# tinyg_g2_breakout.net
KiCad netlist of a schematic drawn in EAGLE
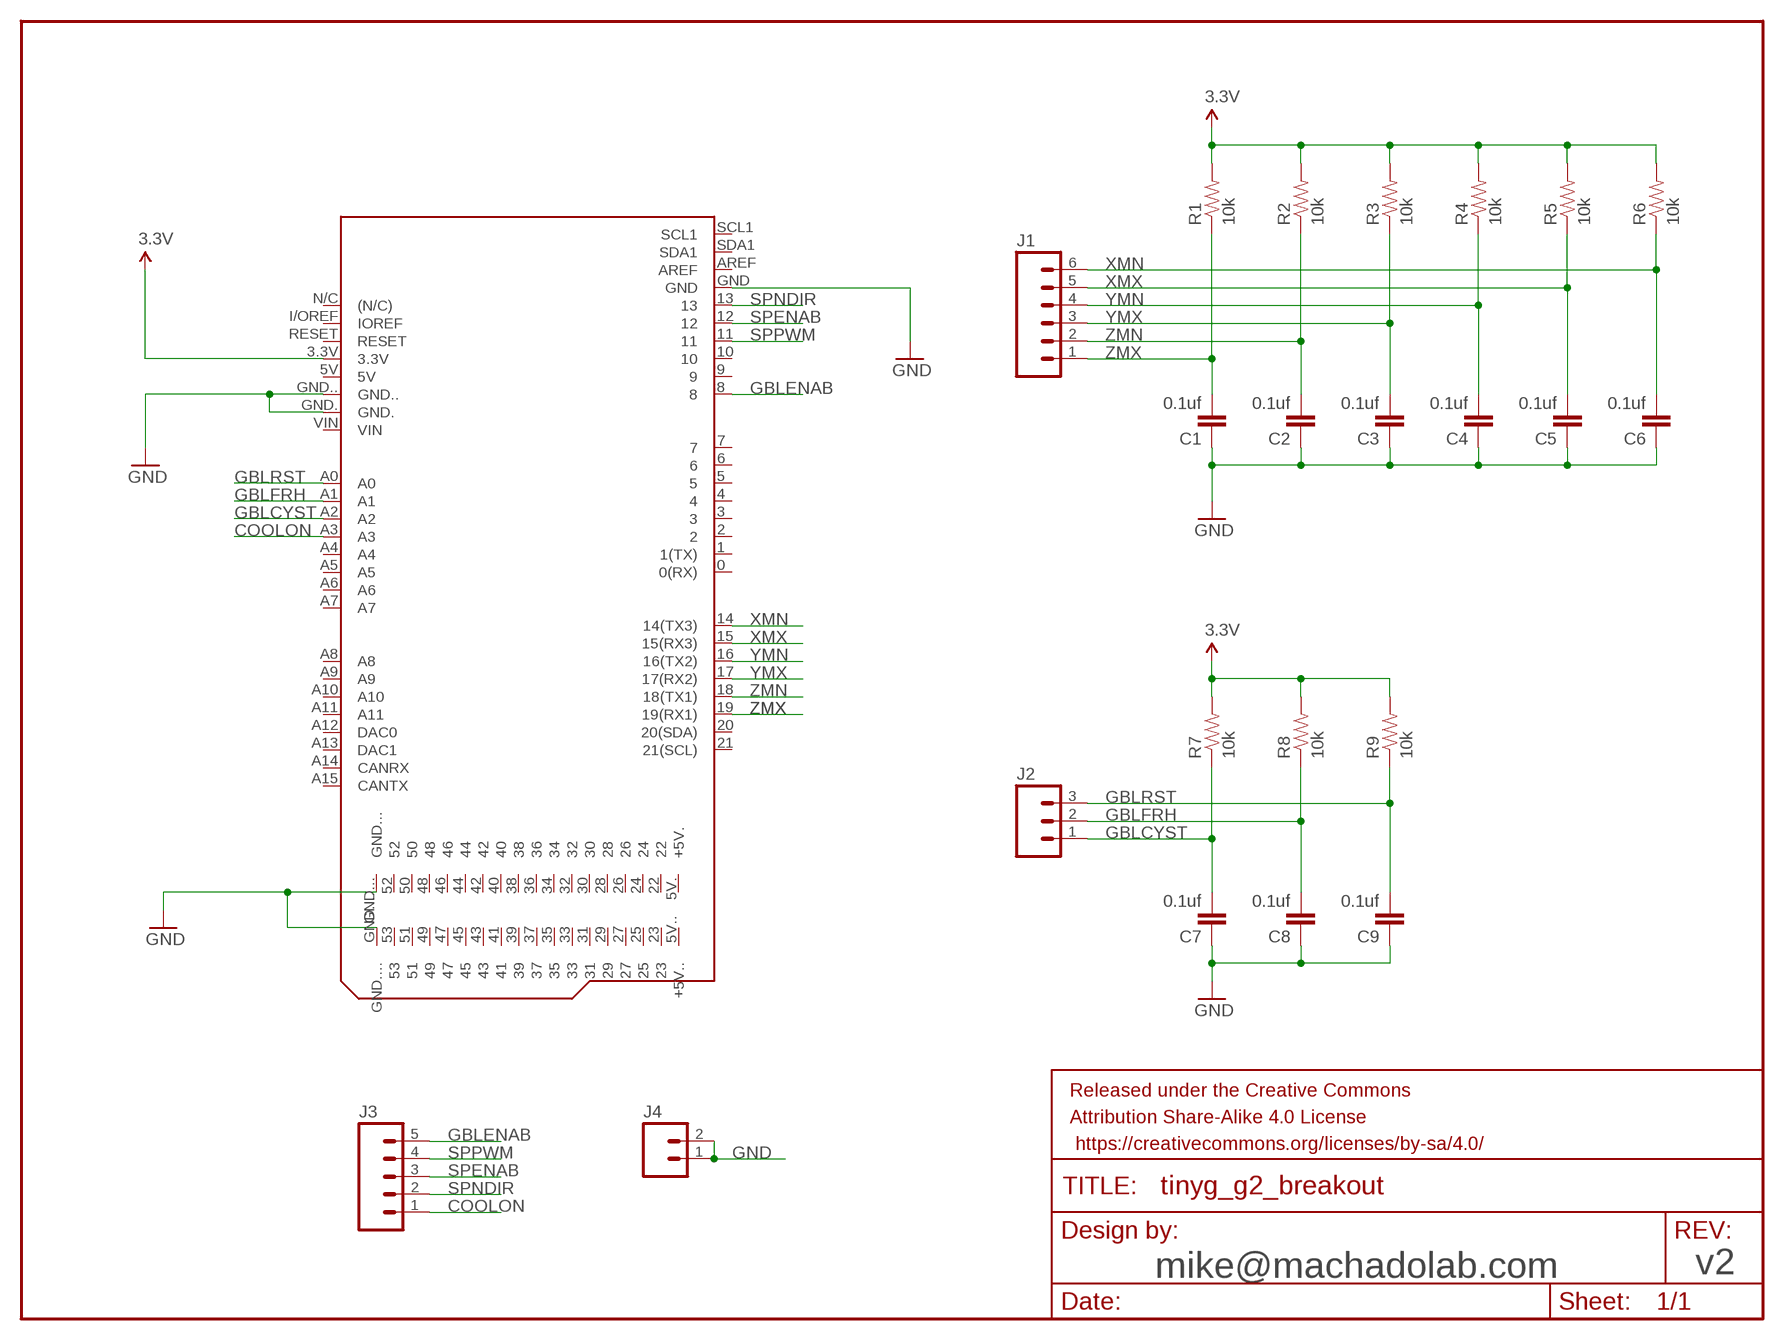
[diagram p0: schematic, sheet 1]

(export (version "E")
  (design (tool "Eeschema 10.0.6"))
  (components
    (comp (ref "C1")
      (value "0.1uf")
      (footprint "eagle-import:CAP-PTH-SMALL")
      (libsource (lib "eagle-import") (part "CAPPTH"))
    )
    (comp (ref "C2")
      (value "0.1uf")
      (footprint "eagle-import:CAP-PTH-SMALL")
      (libsource (lib "eagle-import") (part "CAPPTH"))
    )
    (comp (ref "C3")
      (value "0.1uf")
      (footprint "eagle-import:CAP-PTH-SMALL")
      (libsource (lib "eagle-import") (part "CAPPTH"))
    )
    (comp (ref "C4")
      (value "0.1uf")
      (footprint "eagle-import:CAP-PTH-SMALL")
      (libsource (lib "eagle-import") (part "CAPPTH"))
    )
    (comp (ref "C5")
      (value "0.1uf")
      (footprint "eagle-import:CAP-PTH-SMALL")
      (libsource (lib "eagle-import") (part "CAPPTH"))
    )
    (comp (ref "C6")
      (value "0.1uf")
      (footprint "eagle-import:CAP-PTH-SMALL")
      (libsource (lib "eagle-import") (part "CAPPTH"))
    )
    (comp (ref "C7")
      (value "0.1uf")
      (footprint "eagle-import:CAP-PTH-SMALL")
      (libsource (lib "eagle-import") (part "CAPPTH"))
    )
    (comp (ref "C8")
      (value "0.1uf")
      (footprint "eagle-import:CAP-PTH-SMALL")
      (libsource (lib "eagle-import") (part "CAPPTH"))
    )
    (comp (ref "C9")
      (value "0.1uf")
      (footprint "eagle-import:CAP-PTH-SMALL")
      (libsource (lib "eagle-import") (part "CAPPTH"))
    )
    (comp (ref "FRAME1")
      (value "v1")
      (footprint "eagle-import:CREATIVE_COMMONS")
      (libsource (lib "eagle-import") (part "FRAME-LETTER"))
    )
    (comp (ref "J1")
      (value "M06SILK_FEMALE_PTH")
      (footprint "eagle-import:1X06")
      (libsource (lib "eagle-import") (part "M06SILK_FEMALE_PTH"))
    )
    (comp (ref "J2")
      (value "M03PTH")
      (footprint "eagle-import:1X03")
      (libsource (lib "eagle-import") (part "M03PTH"))
    )
    (comp (ref "J3")
      (value "M05PTH")
      (footprint "eagle-import:1X05")
      (libsource (lib "eagle-import") (part "M05PTH"))
    )
    (comp (ref "J4")
      (value "M02PTH")
      (footprint "eagle-import:1X02")
      (libsource (lib "eagle-import") (part "M02PTH"))
    )
    (comp (ref "PCB1")
      (value "ARDUINO_DUE_SHIELD")
      (footprint "eagle-import:ARDUINO_DUE_SHIELD")
      (libsource (lib "eagle-import") (part "ARDUINO_DUE_SHIELD"))
    )
    (comp (ref "R1")
      (value "10k")
      (footprint "eagle-import:AXIAL-0.3")
      (libsource (lib "eagle-import") (part "RESISTORAXIAL-0.3"))
    )
    (comp (ref "R2")
      (value "10k")
      (footprint "eagle-import:AXIAL-0.3")
      (libsource (lib "eagle-import") (part "RESISTORAXIAL-0.3"))
    )
    (comp (ref "R3")
      (value "10k")
      (footprint "eagle-import:AXIAL-0.3")
      (libsource (lib "eagle-import") (part "RESISTORAXIAL-0.3"))
    )
    (comp (ref "R4")
      (value "10k")
      (footprint "eagle-import:AXIAL-0.3")
      (libsource (lib "eagle-import") (part "RESISTORAXIAL-0.3"))
    )
    (comp (ref "R5")
      (value "10k")
      (footprint "eagle-import:AXIAL-0.3")
      (libsource (lib "eagle-import") (part "RESISTORAXIAL-0.3"))
    )
    (comp (ref "R6")
      (value "10k")
      (footprint "eagle-import:AXIAL-0.3")
      (libsource (lib "eagle-import") (part "RESISTORAXIAL-0.3"))
    )
    (comp (ref "R7")
      (value "10k")
      (footprint "eagle-import:AXIAL-0.3")
      (libsource (lib "eagle-import") (part "RESISTORAXIAL-0.3"))
    )
    (comp (ref "R8")
      (value "10k")
      (footprint "eagle-import:AXIAL-0.3")
      (libsource (lib "eagle-import") (part "RESISTORAXIAL-0.3"))
    )
    (comp (ref "R9")
      (value "10k")
      (footprint "eagle-import:AXIAL-0.3")
      (libsource (lib "eagle-import") (part "RESISTORAXIAL-0.3"))
    )
  )
  (nets
    (net (code "1") (name "/COOLON") (class "Default")
      (node (ref "J3") (pin "1") (pinfunction "1_1") (pintype "passive"))
      (node (ref "PCB1") (pin "A3") (pinfunction "A3_A3") (pintype "bidirectional"))
    )
    (net (code "2") (name "/GBLCYST") (class "Default")
      (node (ref "C7") (pin "2") (pinfunction "2_2") (pintype "passive"))
      (node (ref "J2") (pin "1") (pinfunction "1_1") (pintype "passive"))
      (node (ref "PCB1") (pin "A2") (pinfunction "A2_A2") (pintype "bidirectional"))
      (node (ref "R7") (pin "P$1") (pinfunction "1_P$1") (pintype "passive"))
    )
    (net (code "3") (name "/GBLENAB") (class "Default")
      (node (ref "J3") (pin "5") (pinfunction "5_5") (pintype "passive"))
      (node (ref "PCB1") (pin "8") (pinfunction "8_8") (pintype "bidirectional"))
    )
    (net (code "4") (name "/GBLFRH") (class "Default")
      (node (ref "C8") (pin "2") (pinfunction "2_2") (pintype "passive"))
      (node (ref "J2") (pin "2") (pinfunction "2_2") (pintype "passive"))
      (node (ref "PCB1") (pin "A1") (pinfunction "A1_A1") (pintype "bidirectional"))
      (node (ref "R8") (pin "P$1") (pinfunction "1_P$1") (pintype "passive"))
    )
    (net (code "5") (name "/GBLRST") (class "Default")
      (node (ref "C9") (pin "2") (pinfunction "2_2") (pintype "passive"))
      (node (ref "J2") (pin "3") (pinfunction "3_3") (pintype "passive"))
      (node (ref "PCB1") (pin "A0") (pinfunction "A0_A0") (pintype "bidirectional"))
      (node (ref "R9") (pin "P$1") (pinfunction "1_P$1") (pintype "passive"))
    )
    (net (code "6") (name "/SPENAB") (class "Default")
      (node (ref "J3") (pin "3") (pinfunction "3_3") (pintype "passive"))
      (node (ref "PCB1") (pin "12") (pinfunction "12_12") (pintype "bidirectional"))
    )
    (net (code "7") (name "/SPNDIR") (class "Default")
      (node (ref "J3") (pin "2") (pinfunction "2_2") (pintype "passive"))
      (node (ref "PCB1") (pin "13") (pinfunction "13_13") (pintype "bidirectional"))
    )
    (net (code "8") (name "/SPPWM") (class "Default")
      (node (ref "J3") (pin "4") (pinfunction "4_4") (pintype "passive"))
      (node (ref "PCB1") (pin "11") (pinfunction "11_11") (pintype "bidirectional"))
    )
    (net (code "9") (name "/XMN") (class "Default")
      (node (ref "C6") (pin "2") (pinfunction "2_2") (pintype "passive"))
      (node (ref "J1") (pin "6") (pinfunction "6_6") (pintype "passive"))
      (node (ref "PCB1") (pin "14") (pinfunction "14(TX3)_14") (pintype "bidirectional"))
      (node (ref "R6") (pin "P$1") (pinfunction "1_P$1") (pintype "passive"))
    )
    (net (code "10") (name "/XMX") (class "Default")
      (node (ref "C5") (pin "2") (pinfunction "2_2") (pintype "passive"))
      (node (ref "J1") (pin "5") (pinfunction "5_5") (pintype "passive"))
      (node (ref "PCB1") (pin "15") (pinfunction "15(RX3)_15") (pintype "bidirectional"))
      (node (ref "R5") (pin "P$1") (pinfunction "1_P$1") (pintype "passive"))
    )
    (net (code "11") (name "/YMN") (class "Default")
      (node (ref "C4") (pin "2") (pinfunction "2_2") (pintype "passive"))
      (node (ref "J1") (pin "4") (pinfunction "4_4") (pintype "passive"))
      (node (ref "PCB1") (pin "16") (pinfunction "16(TX2)_16") (pintype "bidirectional"))
      (node (ref "R4") (pin "P$1") (pinfunction "1_P$1") (pintype "passive"))
    )
    (net (code "12") (name "/YMX") (class "Default")
      (node (ref "C3") (pin "2") (pinfunction "2_2") (pintype "passive"))
      (node (ref "J1") (pin "3") (pinfunction "3_3") (pintype "passive"))
      (node (ref "PCB1") (pin "17") (pinfunction "17(RX2)_17") (pintype "bidirectional"))
      (node (ref "R3") (pin "P$1") (pinfunction "1_P$1") (pintype "passive"))
    )
    (net (code "13") (name "/ZMN") (class "Default")
      (node (ref "C2") (pin "2") (pinfunction "2_2") (pintype "passive"))
      (node (ref "J1") (pin "2") (pinfunction "2_2") (pintype "passive"))
      (node (ref "PCB1") (pin "18") (pinfunction "18(TX1)_18") (pintype "bidirectional"))
      (node (ref "R2") (pin "P$1") (pinfunction "1_P$1") (pintype "passive"))
    )
    (net (code "14") (name "/ZMX") (class "Default")
      (node (ref "C1") (pin "2") (pinfunction "2_2") (pintype "passive"))
      (node (ref "J1") (pin "1") (pinfunction "1_1") (pintype "passive"))
      (node (ref "PCB1") (pin "19") (pinfunction "19(RX1)_19") (pintype "bidirectional"))
      (node (ref "R1") (pin "P$1") (pinfunction "1_P$1") (pintype "passive"))
    )
    (net (code "15") (name "3.3V") (class "Default")
      (node (ref "PCB1") (pin "3.3V") (pinfunction "3.3V_3.3V") (pintype "bidirectional"))
      (node (ref "R1") (pin "P$2") (pinfunction "2_P$2") (pintype "passive"))
      (node (ref "R2") (pin "P$2") (pinfunction "2_P$2") (pintype "passive"))
      (node (ref "R3") (pin "P$2") (pinfunction "2_P$2") (pintype "passive"))
      (node (ref "R4") (pin "P$2") (pinfunction "2_P$2") (pintype "passive"))
      (node (ref "R5") (pin "P$2") (pinfunction "2_P$2") (pintype "passive"))
      (node (ref "R6") (pin "P$2") (pinfunction "2_P$2") (pintype "passive"))
      (node (ref "R7") (pin "P$2") (pinfunction "2_P$2") (pintype "passive"))
      (node (ref "R8") (pin "P$2") (pinfunction "2_P$2") (pintype "passive"))
      (node (ref "R9") (pin "P$2") (pinfunction "2_P$2") (pintype "passive"))
    )
    (net (code "16") (name "GND") (class "Default")
      (node (ref "C1") (pin "1") (pinfunction "1_1") (pintype "passive"))
      (node (ref "C2") (pin "1") (pinfunction "1_1") (pintype "passive"))
      (node (ref "C3") (pin "1") (pinfunction "1_1") (pintype "passive"))
      (node (ref "C4") (pin "1") (pinfunction "1_1") (pintype "passive"))
      (node (ref "C5") (pin "1") (pinfunction "1_1") (pintype "passive"))
      (node (ref "C6") (pin "1") (pinfunction "1_1") (pintype "passive"))
      (node (ref "C7") (pin "1") (pinfunction "1_1") (pintype "passive"))
      (node (ref "C8") (pin "1") (pinfunction "1_1") (pintype "passive"))
      (node (ref "C9") (pin "1") (pinfunction "1_1") (pintype "passive"))
      (node (ref "J4") (pin "1") (pinfunction "1_1") (pintype "passive"))
      (node (ref "J4") (pin "2") (pinfunction "2_2") (pintype "passive"))
      (node (ref "PCB1") (pin "GND") (pinfunction "GND_GND") (pintype "bidirectional"))
      (node (ref "PCB1") (pin "GND.") (pinfunction "GND._GND.") (pintype "bidirectional"))
      (node (ref "PCB1") (pin "GND..") (pinfunction "GND.._GND..") (pintype "bidirectional"))
      (node (ref "PCB1") (pin "GND...") (pinfunction "GND..._GND...") (pintype "bidirectional"))
      (node (ref "PCB1") (pin "GND....") (pinfunction "GND...._GND....") (pintype "bidirectional"))
    )
    (net (code "17") (name "unconnected-(PCB1-(N{slash}C)-PadN{slash}C)") (class "Default")
      (node (ref "PCB1") (pin "N/C") (pinfunction "(N/C)_N/C") (pintype "bidirectional"))
    )
    (net (code "18") (name "unconnected-(PCB1-+5V.-Pad5V.)") (class "Default")
      (node (ref "PCB1") (pin "5V.") (pinfunction "+5V._5V.") (pintype "bidirectional"))
    )
    (net (code "19") (name "unconnected-(PCB1-+5V..-Pad5V..)") (class "Default")
      (node (ref "PCB1") (pin "5V..") (pinfunction "+5V.._5V..") (pintype "bidirectional"))
    )
    (net (code "20") (name "unconnected-(PCB1-0(RX)-Pad0)") (class "Default")
      (node (ref "PCB1") (pin "0") (pinfunction "0(RX)_0") (pintype "bidirectional"))
    )
    (net (code "21") (name "unconnected-(PCB1-1(TX)-Pad1)") (class "Default")
      (node (ref "PCB1") (pin "1") (pinfunction "1(TX)_1") (pintype "bidirectional"))
    )
    (net (code "22") (name "unconnected-(PCB1-20(SDA)-Pad20)") (class "Default")
      (node (ref "PCB1") (pin "20") (pinfunction "20(SDA)_20") (pintype "bidirectional"))
    )
    (net (code "23") (name "unconnected-(PCB1-21(SCL)-Pad21)") (class "Default")
      (node (ref "PCB1") (pin "21") (pinfunction "21(SCL)_21") (pintype "bidirectional"))
    )
    (net (code "24") (name "unconnected-(PCB1-CANRX-PadA14)") (class "Default")
      (node (ref "PCB1") (pin "A14") (pinfunction "CANRX_A14") (pintype "bidirectional"))
    )
    (net (code "25") (name "unconnected-(PCB1-CANTX-PadA15)") (class "Default")
      (node (ref "PCB1") (pin "A15") (pinfunction "CANTX_A15") (pintype "bidirectional"))
    )
    (net (code "26") (name "unconnected-(PCB1-DAC0-PadA12)") (class "Default")
      (node (ref "PCB1") (pin "A12") (pinfunction "DAC0_A12") (pintype "bidirectional"))
    )
    (net (code "27") (name "unconnected-(PCB1-DAC1-PadA13)") (class "Default")
      (node (ref "PCB1") (pin "A13") (pinfunction "DAC1_A13") (pintype "bidirectional"))
    )
    (net (code "28") (name "unconnected-(PCB1-IOREF-PadI{slash}OREF)") (class "Default")
      (node (ref "PCB1") (pin "I/OREF") (pinfunction "IOREF_I/OREF") (pintype "bidirectional"))
    )
    (net (code "29") (name "unconnected-(PCB1-Pad2)") (class "Default")
      (node (ref "PCB1") (pin "2") (pinfunction "2_2") (pintype "bidirectional"))
    )
    (net (code "30") (name "unconnected-(PCB1-Pad3)") (class "Default")
      (node (ref "PCB1") (pin "3") (pinfunction "3_3") (pintype "bidirectional"))
    )
    (net (code "31") (name "unconnected-(PCB1-Pad4)") (class "Default")
      (node (ref "PCB1") (pin "4") (pinfunction "4_4") (pintype "bidirectional"))
    )
    (net (code "32") (name "unconnected-(PCB1-Pad5)") (class "Default")
      (node (ref "PCB1") (pin "5") (pinfunction "5_5") (pintype "bidirectional"))
    )
    (net (code "33") (name "unconnected-(PCB1-Pad5V)") (class "Default")
      (node (ref "PCB1") (pin "5V") (pinfunction "5V_5V") (pintype "bidirectional"))
    )
    (net (code "34") (name "unconnected-(PCB1-Pad6)") (class "Default")
      (node (ref "PCB1") (pin "6") (pinfunction "6_6") (pintype "bidirectional"))
    )
    (net (code "35") (name "unconnected-(PCB1-Pad7)") (class "Default")
      (node (ref "PCB1") (pin "7") (pinfunction "7_7") (pintype "bidirectional"))
    )
    (net (code "36") (name "unconnected-(PCB1-Pad9)") (class "Default")
      (node (ref "PCB1") (pin "9") (pinfunction "9_9") (pintype "bidirectional"))
    )
    (net (code "37") (name "unconnected-(PCB1-Pad10)") (class "Default")
      (node (ref "PCB1") (pin "10") (pinfunction "10_10") (pintype "bidirectional"))
    )
    (net (code "38") (name "unconnected-(PCB1-Pad22)") (class "Default")
      (node (ref "PCB1") (pin "22") (pinfunction "22_22") (pintype "bidirectional"))
    )
    (net (code "39") (name "unconnected-(PCB1-Pad23)") (class "Default")
      (node (ref "PCB1") (pin "23") (pinfunction "23_23") (pintype "bidirectional"))
    )
    (net (code "40") (name "unconnected-(PCB1-Pad24)") (class "Default")
      (node (ref "PCB1") (pin "24") (pinfunction "24_24") (pintype "bidirectional"))
    )
    (net (code "41") (name "unconnected-(PCB1-Pad25)") (class "Default")
      (node (ref "PCB1") (pin "25") (pinfunction "25_25") (pintype "bidirectional"))
    )
    (net (code "42") (name "unconnected-(PCB1-Pad26)") (class "Default")
      (node (ref "PCB1") (pin "26") (pinfunction "26_26") (pintype "bidirectional"))
    )
    (net (code "43") (name "unconnected-(PCB1-Pad27)") (class "Default")
      (node (ref "PCB1") (pin "27") (pinfunction "27_27") (pintype "bidirectional"))
    )
    (net (code "44") (name "unconnected-(PCB1-Pad28)") (class "Default")
      (node (ref "PCB1") (pin "28") (pinfunction "28_28") (pintype "bidirectional"))
    )
    (net (code "45") (name "unconnected-(PCB1-Pad29)") (class "Default")
      (node (ref "PCB1") (pin "29") (pinfunction "29_29") (pintype "bidirectional"))
    )
    (net (code "46") (name "unconnected-(PCB1-Pad30)") (class "Default")
      (node (ref "PCB1") (pin "30") (pinfunction "30_30") (pintype "bidirectional"))
    )
    (net (code "47") (name "unconnected-(PCB1-Pad31)") (class "Default")
      (node (ref "PCB1") (pin "31") (pinfunction "31_31") (pintype "bidirectional"))
    )
    (net (code "48") (name "unconnected-(PCB1-Pad32)") (class "Default")
      (node (ref "PCB1") (pin "32") (pinfunction "32_32") (pintype "bidirectional"))
    )
    (net (code "49") (name "unconnected-(PCB1-Pad33)") (class "Default")
      (node (ref "PCB1") (pin "33") (pinfunction "33_33") (pintype "bidirectional"))
    )
    (net (code "50") (name "unconnected-(PCB1-Pad34)") (class "Default")
      (node (ref "PCB1") (pin "34") (pinfunction "34_34") (pintype "bidirectional"))
    )
    (net (code "51") (name "unconnected-(PCB1-Pad35)") (class "Default")
      (node (ref "PCB1") (pin "35") (pinfunction "35_35") (pintype "bidirectional"))
    )
    (net (code "52") (name "unconnected-(PCB1-Pad36)") (class "Default")
      (node (ref "PCB1") (pin "36") (pinfunction "36_36") (pintype "bidirectional"))
    )
    (net (code "53") (name "unconnected-(PCB1-Pad37)") (class "Default")
      (node (ref "PCB1") (pin "37") (pinfunction "37_37") (pintype "bidirectional"))
    )
    (net (code "54") (name "unconnected-(PCB1-Pad38)") (class "Default")
      (node (ref "PCB1") (pin "38") (pinfunction "38_38") (pintype "bidirectional"))
    )
    (net (code "55") (name "unconnected-(PCB1-Pad39)") (class "Default")
      (node (ref "PCB1") (pin "39") (pinfunction "39_39") (pintype "bidirectional"))
    )
    (net (code "56") (name "unconnected-(PCB1-Pad40)") (class "Default")
      (node (ref "PCB1") (pin "40") (pinfunction "40_40") (pintype "bidirectional"))
    )
    (net (code "57") (name "unconnected-(PCB1-Pad41)") (class "Default")
      (node (ref "PCB1") (pin "41") (pinfunction "41_41") (pintype "bidirectional"))
    )
    (net (code "58") (name "unconnected-(PCB1-Pad42)") (class "Default")
      (node (ref "PCB1") (pin "42") (pinfunction "42_42") (pintype "bidirectional"))
    )
    (net (code "59") (name "unconnected-(PCB1-Pad43)") (class "Default")
      (node (ref "PCB1") (pin "43") (pinfunction "43_43") (pintype "bidirectional"))
    )
    (net (code "60") (name "unconnected-(PCB1-Pad44)") (class "Default")
      (node (ref "PCB1") (pin "44") (pinfunction "44_44") (pintype "bidirectional"))
    )
    (net (code "61") (name "unconnected-(PCB1-Pad45)") (class "Default")
      (node (ref "PCB1") (pin "45") (pinfunction "45_45") (pintype "bidirectional"))
    )
    (net (code "62") (name "unconnected-(PCB1-Pad46)") (class "Default")
      (node (ref "PCB1") (pin "46") (pinfunction "46_46") (pintype "bidirectional"))
    )
    (net (code "63") (name "unconnected-(PCB1-Pad47)") (class "Default")
      (node (ref "PCB1") (pin "47") (pinfunction "47_47") (pintype "bidirectional"))
    )
    (net (code "64") (name "unconnected-(PCB1-Pad48)") (class "Default")
      (node (ref "PCB1") (pin "48") (pinfunction "48_48") (pintype "bidirectional"))
    )
    (net (code "65") (name "unconnected-(PCB1-Pad49)") (class "Default")
      (node (ref "PCB1") (pin "49") (pinfunction "49_49") (pintype "bidirectional"))
    )
    (net (code "66") (name "unconnected-(PCB1-Pad50)") (class "Default")
      (node (ref "PCB1") (pin "50") (pinfunction "50_50") (pintype "bidirectional"))
    )
    (net (code "67") (name "unconnected-(PCB1-Pad51)") (class "Default")
      (node (ref "PCB1") (pin "51") (pinfunction "51_51") (pintype "bidirectional"))
    )
    (net (code "68") (name "unconnected-(PCB1-Pad52)") (class "Default")
      (node (ref "PCB1") (pin "52") (pinfunction "52_52") (pintype "bidirectional"))
    )
    (net (code "69") (name "unconnected-(PCB1-Pad53)") (class "Default")
      (node (ref "PCB1") (pin "53") (pinfunction "53_53") (pintype "bidirectional"))
    )
    (net (code "70") (name "unconnected-(PCB1-PadA4)") (class "Default")
      (node (ref "PCB1") (pin "A4") (pinfunction "A4_A4") (pintype "bidirectional"))
    )
    (net (code "71") (name "unconnected-(PCB1-PadA5)") (class "Default")
      (node (ref "PCB1") (pin "A5") (pinfunction "A5_A5") (pintype "bidirectional"))
    )
    (net (code "72") (name "unconnected-(PCB1-PadA6)") (class "Default")
      (node (ref "PCB1") (pin "A6") (pinfunction "A6_A6") (pintype "bidirectional"))
    )
    (net (code "73") (name "unconnected-(PCB1-PadA7)") (class "Default")
      (node (ref "PCB1") (pin "A7") (pinfunction "A7_A7") (pintype "bidirectional"))
    )
    (net (code "74") (name "unconnected-(PCB1-PadA8)") (class "Default")
      (node (ref "PCB1") (pin "A8") (pinfunction "A8_A8") (pintype "bidirectional"))
    )
    (net (code "75") (name "unconnected-(PCB1-PadA9)") (class "Default")
      (node (ref "PCB1") (pin "A9") (pinfunction "A9_A9") (pintype "bidirectional"))
    )
    (net (code "76") (name "unconnected-(PCB1-PadA10)") (class "Default")
      (node (ref "PCB1") (pin "A10") (pinfunction "A10_A10") (pintype "bidirectional"))
    )
    (net (code "77") (name "unconnected-(PCB1-PadA11)") (class "Default")
      (node (ref "PCB1") (pin "A11") (pinfunction "A11_A11") (pintype "bidirectional"))
    )
    (net (code "78") (name "unconnected-(PCB1-PadAREF)") (class "Default")
      (node (ref "PCB1") (pin "AREF") (pinfunction "AREF_AREF") (pintype "bidirectional"))
    )
    (net (code "79") (name "unconnected-(PCB1-PadRESET)") (class "Default")
      (node (ref "PCB1") (pin "RESET") (pinfunction "RESET_RESET") (pintype "bidirectional"))
    )
    (net (code "80") (name "unconnected-(PCB1-PadSCL1)") (class "Default")
      (node (ref "PCB1") (pin "SCL1") (pinfunction "SCL1_SCL1") (pintype "bidirectional"))
    )
    (net (code "81") (name "unconnected-(PCB1-PadSDA1)") (class "Default")
      (node (ref "PCB1") (pin "SDA1") (pinfunction "SDA1_SDA1") (pintype "bidirectional"))
    )
    (net (code "82") (name "unconnected-(PCB1-PadVIN)") (class "Default")
      (node (ref "PCB1") (pin "VIN") (pinfunction "VIN_VIN") (pintype "bidirectional"))
    )
  )
)
